# DIY_BLE_Keyboard.net
KiCad netlist of a schematic drawn in Altium Designer
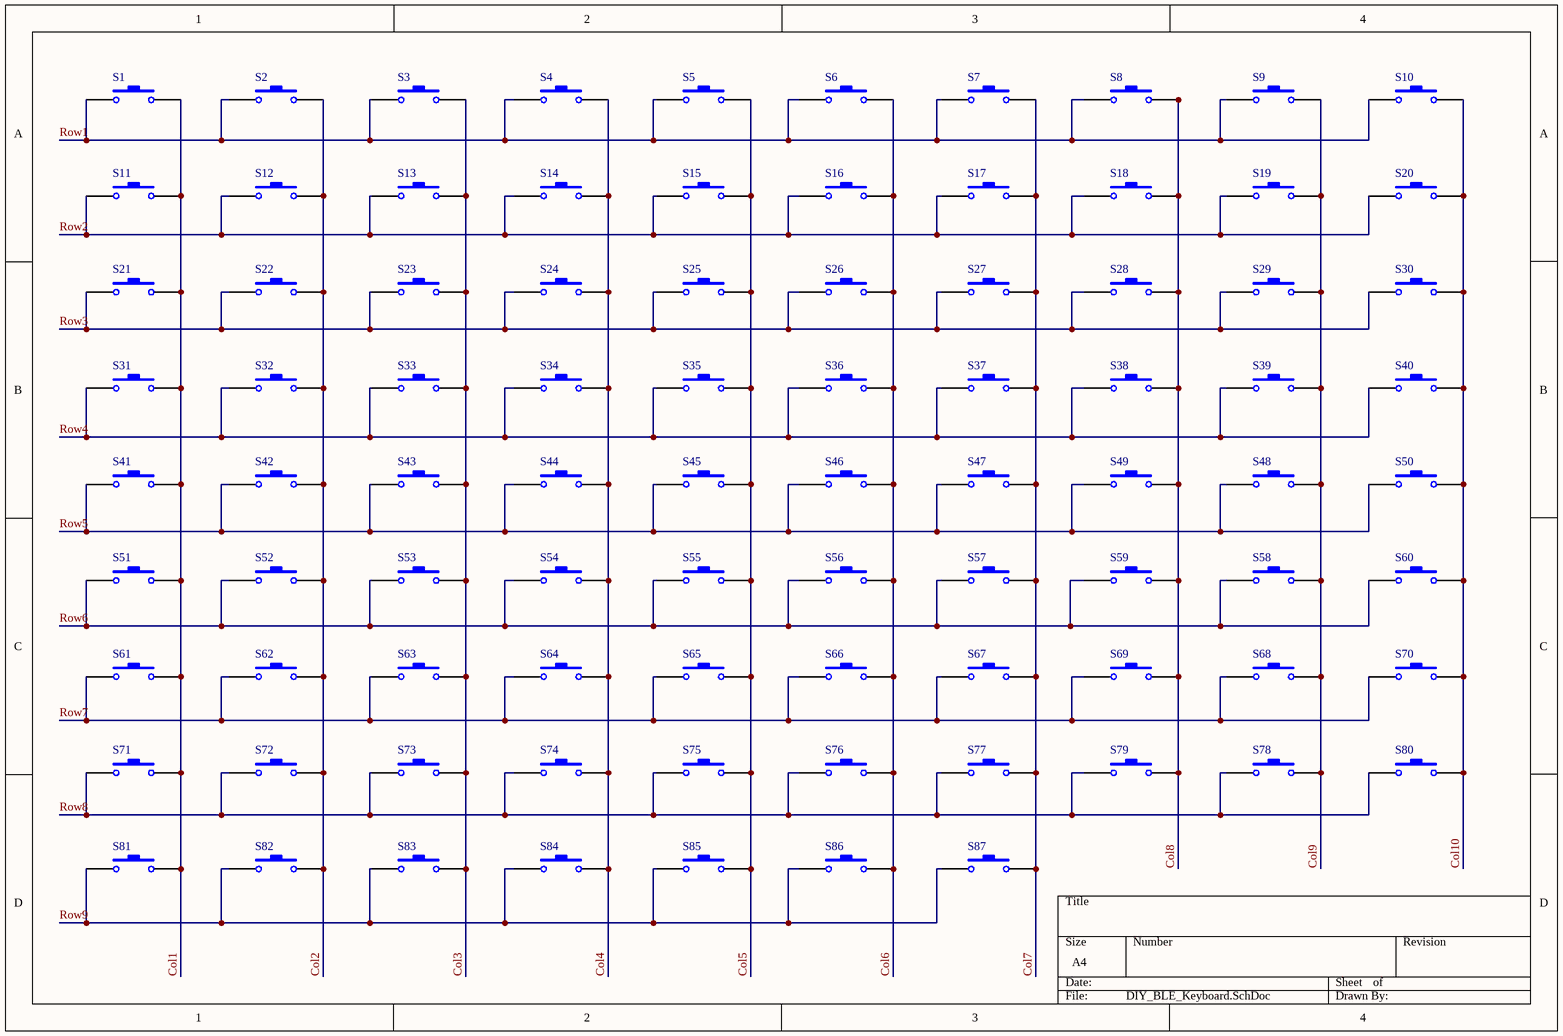
[diagram p0: DIY_BLE_Keyboard.SchDoc]

(export (version "E")
  (design (tool "Eeschema 10.0.6"))
  (components
    (comp (ref "S1")
      (value "SW-PB")
      (footprint "MX_SW-4")
      (description "Switch")
      (fields (field (name "PUBLISHER") "Altium Limited"))
      (libsource (lib "Miscellaneous Devices") (part "SW-PB"))
    )
    (comp (ref "S2")
      (value "SW-PB")
      (footprint "MX_SW-4")
      (description "Switch")
      (fields (field (name "PUBLISHER") "Altium Limited"))
      (libsource (lib "Miscellaneous Devices") (part "SW-PB"))
    )
    (comp (ref "S3")
      (value "SW-PB")
      (footprint "MX_SW-4")
      (description "Switch")
      (fields (field (name "PUBLISHER") "Altium Limited"))
      (libsource (lib "Miscellaneous Devices") (part "SW-PB"))
    )
    (comp (ref "S4")
      (value "SW-PB")
      (footprint "MX_SW-4")
      (description "Switch")
      (fields (field (name "PUBLISHER") "Altium Limited"))
      (libsource (lib "Miscellaneous Devices") (part "SW-PB"))
    )
    (comp (ref "S5")
      (value "SW-PB")
      (footprint "MX_SW-4")
      (description "Switch")
      (fields (field (name "PUBLISHER") "Altium Limited"))
      (libsource (lib "Miscellaneous Devices") (part "SW-PB"))
    )
    (comp (ref "S6")
      (value "SW-PB")
      (footprint "MX_SW-4")
      (description "Switch")
      (fields (field (name "PUBLISHER") "Altium Limited"))
      (libsource (lib "Miscellaneous Devices") (part "SW-PB"))
    )
    (comp (ref "S7")
      (value "SW-PB")
      (footprint "MX_SW-4")
      (description "Switch")
      (fields (field (name "PUBLISHER") "Altium Limited"))
      (libsource (lib "Miscellaneous Devices") (part "SW-PB"))
    )
    (comp (ref "S8")
      (value "SW-PB")
      (footprint "MX_SW-4")
      (description "Switch")
      (fields (field (name "PUBLISHER") "Altium Limited"))
      (libsource (lib "Miscellaneous Devices") (part "SW-PB"))
    )
    (comp (ref "S9")
      (value "SW-PB")
      (footprint "MX_SW-4")
      (description "Switch")
      (fields (field (name "PUBLISHER") "Altium Limited"))
      (libsource (lib "Miscellaneous Devices") (part "SW-PB"))
    )
    (comp (ref "S10")
      (value "SW-PB")
      (footprint "MX_SW-4")
      (description "Switch")
      (fields (field (name "PUBLISHER") "Altium Limited"))
      (libsource (lib "Miscellaneous Devices") (part "SW-PB"))
    )
    (comp (ref "S11")
      (value "SW-PB")
      (footprint "MX_SW-4")
      (description "Switch")
      (fields (field (name "PUBLISHER") "Altium Limited"))
      (libsource (lib "Miscellaneous Devices") (part "SW-PB"))
    )
    (comp (ref "S12")
      (value "SW-PB")
      (footprint "MX_SW-4")
      (description "Switch")
      (fields (field (name "PUBLISHER") "Altium Limited"))
      (libsource (lib "Miscellaneous Devices") (part "SW-PB"))
    )
    (comp (ref "S13")
      (value "SW-PB")
      (footprint "MX_SW-4")
      (description "Switch")
      (fields (field (name "PUBLISHER") "Altium Limited"))
      (libsource (lib "Miscellaneous Devices") (part "SW-PB"))
    )
    (comp (ref "S14")
      (value "SW-PB")
      (footprint "MX_SW-4")
      (description "Switch")
      (fields (field (name "PUBLISHER") "Altium Limited"))
      (libsource (lib "Miscellaneous Devices") (part "SW-PB"))
    )
    (comp (ref "S15")
      (value "SW-PB")
      (footprint "MX_SW-4")
      (description "Switch")
      (fields (field (name "PUBLISHER") "Altium Limited"))
      (libsource (lib "Miscellaneous Devices") (part "SW-PB"))
    )
    (comp (ref "S16")
      (value "SW-PB")
      (footprint "MX_SW-4")
      (description "Switch")
      (fields (field (name "PUBLISHER") "Altium Limited"))
      (libsource (lib "Miscellaneous Devices") (part "SW-PB"))
    )
    (comp (ref "S17")
      (value "SW-PB")
      (footprint "MX_SW-4")
      (description "Switch")
      (fields (field (name "PUBLISHER") "Altium Limited"))
      (libsource (lib "Miscellaneous Devices") (part "SW-PB"))
    )
    (comp (ref "S18")
      (value "SW-PB")
      (footprint "MX_SW-4")
      (description "Switch")
      (fields (field (name "PUBLISHER") "Altium Limited"))
      (libsource (lib "Miscellaneous Devices") (part "SW-PB"))
    )
    (comp (ref "S19")
      (value "SW-PB")
      (footprint "MX_SW-4")
      (description "Switch")
      (fields (field (name "PUBLISHER") "Altium Limited"))
      (libsource (lib "Miscellaneous Devices") (part "SW-PB"))
    )
    (comp (ref "S20")
      (value "SW-PB")
      (footprint "MX_SW-4")
      (description "Switch")
      (fields (field (name "PUBLISHER") "Altium Limited"))
      (libsource (lib "Miscellaneous Devices") (part "SW-PB"))
    )
    (comp (ref "S21")
      (value "SW-PB")
      (footprint "MX_SW-4")
      (description "Switch")
      (fields (field (name "PUBLISHER") "Altium Limited"))
      (libsource (lib "Miscellaneous Devices") (part "SW-PB"))
    )
    (comp (ref "S22")
      (value "SW-PB")
      (footprint "MX_SW-4")
      (description "Switch")
      (fields (field (name "PUBLISHER") "Altium Limited"))
      (libsource (lib "Miscellaneous Devices") (part "SW-PB"))
    )
    (comp (ref "S23")
      (value "SW-PB")
      (footprint "MX_SW-4")
      (description "Switch")
      (fields (field (name "PUBLISHER") "Altium Limited"))
      (libsource (lib "Miscellaneous Devices") (part "SW-PB"))
    )
    (comp (ref "S24")
      (value "SW-PB")
      (footprint "MX_SW-4")
      (description "Switch")
      (fields (field (name "PUBLISHER") "Altium Limited"))
      (libsource (lib "Miscellaneous Devices") (part "SW-PB"))
    )
    (comp (ref "S25")
      (value "SW-PB")
      (footprint "MX_SW-4")
      (description "Switch")
      (fields (field (name "PUBLISHER") "Altium Limited"))
      (libsource (lib "Miscellaneous Devices") (part "SW-PB"))
    )
    (comp (ref "S26")
      (value "SW-PB")
      (footprint "MX_SW-4")
      (description "Switch")
      (fields (field (name "PUBLISHER") "Altium Limited"))
      (libsource (lib "Miscellaneous Devices") (part "SW-PB"))
    )
    (comp (ref "S27")
      (value "SW-PB")
      (footprint "MX_SW-4")
      (description "Switch")
      (fields (field (name "PUBLISHER") "Altium Limited"))
      (libsource (lib "Miscellaneous Devices") (part "SW-PB"))
    )
    (comp (ref "S28")
      (value "SW-PB")
      (footprint "MX_SW-4")
      (description "Switch")
      (fields (field (name "PUBLISHER") "Altium Limited"))
      (libsource (lib "Miscellaneous Devices") (part "SW-PB"))
    )
    (comp (ref "S29")
      (value "SW-PB")
      (footprint "MX_SW-4")
      (description "Switch")
      (fields (field (name "PUBLISHER") "Altium Limited"))
      (libsource (lib "Miscellaneous Devices") (part "SW-PB"))
    )
    (comp (ref "S30")
      (value "SW-PB")
      (footprint "MX_SW-4")
      (description "Switch")
      (fields (field (name "PUBLISHER") "Altium Limited"))
      (libsource (lib "Miscellaneous Devices") (part "SW-PB"))
    )
    (comp (ref "S31")
      (value "SW-PB")
      (footprint "MX_SW-4")
      (description "Switch")
      (fields (field (name "PUBLISHER") "Altium Limited"))
      (libsource (lib "Miscellaneous Devices") (part "SW-PB"))
    )
    (comp (ref "S32")
      (value "SW-PB")
      (footprint "MX_SW-4")
      (description "Switch")
      (fields (field (name "PUBLISHER") "Altium Limited"))
      (libsource (lib "Miscellaneous Devices") (part "SW-PB"))
    )
    (comp (ref "S33")
      (value "SW-PB")
      (footprint "MX_SW-4")
      (description "Switch")
      (fields (field (name "PUBLISHER") "Altium Limited"))
      (libsource (lib "Miscellaneous Devices") (part "SW-PB"))
    )
    (comp (ref "S34")
      (value "SW-PB")
      (footprint "MX_SW-4")
      (description "Switch")
      (fields (field (name "PUBLISHER") "Altium Limited"))
      (libsource (lib "Miscellaneous Devices") (part "SW-PB"))
    )
    (comp (ref "S35")
      (value "SW-PB")
      (footprint "MX_SW-4")
      (description "Switch")
      (fields (field (name "PUBLISHER") "Altium Limited"))
      (libsource (lib "Miscellaneous Devices") (part "SW-PB"))
    )
    (comp (ref "S36")
      (value "SW-PB")
      (footprint "MX_SW-4")
      (description "Switch")
      (fields (field (name "PUBLISHER") "Altium Limited"))
      (libsource (lib "Miscellaneous Devices") (part "SW-PB"))
    )
    (comp (ref "S37")
      (value "SW-PB")
      (footprint "MX_SW-4")
      (description "Switch")
      (fields (field (name "PUBLISHER") "Altium Limited"))
      (libsource (lib "Miscellaneous Devices") (part "SW-PB"))
    )
    (comp (ref "S38")
      (value "SW-PB")
      (footprint "MX_SW-4")
      (description "Switch")
      (fields (field (name "PUBLISHER") "Altium Limited"))
      (libsource (lib "Miscellaneous Devices") (part "SW-PB"))
    )
    (comp (ref "S39")
      (value "SW-PB")
      (footprint "MX_SW-4")
      (description "Switch")
      (fields (field (name "PUBLISHER") "Altium Limited"))
      (libsource (lib "Miscellaneous Devices") (part "SW-PB"))
    )
    (comp (ref "S40")
      (value "SW-PB")
      (footprint "MX_SW-4")
      (description "Switch")
      (fields (field (name "PUBLISHER") "Altium Limited"))
      (libsource (lib "Miscellaneous Devices") (part "SW-PB"))
    )
    (comp (ref "S41")
      (value "SW-PB")
      (footprint "MX_SW-4")
      (description "Switch")
      (fields (field (name "PUBLISHER") "Altium Limited"))
      (libsource (lib "Miscellaneous Devices") (part "SW-PB"))
    )
    (comp (ref "S42")
      (value "SW-PB")
      (footprint "MX_SW-4")
      (description "Switch")
      (fields (field (name "PUBLISHER") "Altium Limited"))
      (libsource (lib "Miscellaneous Devices") (part "SW-PB"))
    )
    (comp (ref "S43")
      (value "SW-PB")
      (footprint "MX_SW-4")
      (description "Switch")
      (fields (field (name "PUBLISHER") "Altium Limited"))
      (libsource (lib "Miscellaneous Devices") (part "SW-PB"))
    )
    (comp (ref "S44")
      (value "SW-PB")
      (footprint "MX_SW-4")
      (description "Switch")
      (fields (field (name "PUBLISHER") "Altium Limited"))
      (libsource (lib "Miscellaneous Devices") (part "SW-PB"))
    )
    (comp (ref "S45")
      (value "SW-PB")
      (footprint "MX_SW-4")
      (description "Switch")
      (fields (field (name "PUBLISHER") "Altium Limited"))
      (libsource (lib "Miscellaneous Devices") (part "SW-PB"))
    )
    (comp (ref "S46")
      (value "SW-PB")
      (footprint "MX_SW-4")
      (description "Switch")
      (fields (field (name "PUBLISHER") "Altium Limited"))
      (libsource (lib "Miscellaneous Devices") (part "SW-PB"))
    )
    (comp (ref "S47")
      (value "SW-PB")
      (footprint "MX_SW-4")
      (description "Switch")
      (fields (field (name "PUBLISHER") "Altium Limited"))
      (libsource (lib "Miscellaneous Devices") (part "SW-PB"))
    )
    (comp (ref "S48")
      (value "SW-PB")
      (footprint "MX_SW-4")
      (description "Switch")
      (fields (field (name "PUBLISHER") "Altium Limited"))
      (libsource (lib "Miscellaneous Devices") (part "SW-PB"))
    )
    (comp (ref "S49")
      (value "SW-PB")
      (footprint "MX_SW-4")
      (description "Switch")
      (fields (field (name "PUBLISHER") "Altium Limited"))
      (libsource (lib "Miscellaneous Devices") (part "SW-PB"))
    )
    (comp (ref "S50")
      (value "SW-PB")
      (footprint "MX_SW-4")
      (description "Switch")
      (fields (field (name "PUBLISHER") "Altium Limited"))
      (libsource (lib "Miscellaneous Devices") (part "SW-PB"))
    )
    (comp (ref "S51")
      (value "SW-PB")
      (footprint "MX_SW-4")
      (description "Switch")
      (fields (field (name "PUBLISHER") "Altium Limited"))
      (libsource (lib "Miscellaneous Devices") (part "SW-PB"))
    )
    (comp (ref "S52")
      (value "SW-PB")
      (footprint "MX_SW-4")
      (description "Switch")
      (fields (field (name "PUBLISHER") "Altium Limited"))
      (libsource (lib "Miscellaneous Devices") (part "SW-PB"))
    )
    (comp (ref "S53")
      (value "SW-PB")
      (footprint "MX_SW-4")
      (description "Switch")
      (fields (field (name "PUBLISHER") "Altium Limited"))
      (libsource (lib "Miscellaneous Devices") (part "SW-PB"))
    )
    (comp (ref "S54")
      (value "SW-PB")
      (footprint "MX_SW-4")
      (description "Switch")
      (fields (field (name "PUBLISHER") "Altium Limited"))
      (libsource (lib "Miscellaneous Devices") (part "SW-PB"))
    )
    (comp (ref "S55")
      (value "SW-PB")
      (footprint "MX_SW-4")
      (description "Switch")
      (fields (field (name "PUBLISHER") "Altium Limited"))
      (libsource (lib "Miscellaneous Devices") (part "SW-PB"))
    )
    (comp (ref "S56")
      (value "SW-PB")
      (footprint "MX_SW-4")
      (description "Switch")
      (fields (field (name "PUBLISHER") "Altium Limited"))
      (libsource (lib "Miscellaneous Devices") (part "SW-PB"))
    )
    (comp (ref "S57")
      (value "SW-PB")
      (footprint "MX_SW-4")
      (description "Switch")
      (fields (field (name "PUBLISHER") "Altium Limited"))
      (libsource (lib "Miscellaneous Devices") (part "SW-PB"))
    )
    (comp (ref "S58")
      (value "SW-PB")
      (footprint "MX_SW-4")
      (description "Switch")
      (fields (field (name "PUBLISHER") "Altium Limited"))
      (libsource (lib "Miscellaneous Devices") (part "SW-PB"))
    )
    (comp (ref "S59")
      (value "SW-PB")
      (footprint "MX_SW-4")
      (description "Switch")
      (fields (field (name "PUBLISHER") "Altium Limited"))
      (libsource (lib "Miscellaneous Devices") (part "SW-PB"))
    )
    (comp (ref "S60")
      (value "SW-PB")
      (footprint "MX_SW-4")
      (description "Switch")
      (fields (field (name "PUBLISHER") "Altium Limited"))
      (libsource (lib "Miscellaneous Devices") (part "SW-PB"))
    )
    (comp (ref "S61")
      (value "SW-PB")
      (footprint "MX_SW-4")
      (description "Switch")
      (fields (field (name "PUBLISHER") "Altium Limited"))
      (libsource (lib "Miscellaneous Devices") (part "SW-PB"))
    )
    (comp (ref "S62")
      (value "SW-PB")
      (footprint "MX_SW-4")
      (description "Switch")
      (fields (field (name "PUBLISHER") "Altium Limited"))
      (libsource (lib "Miscellaneous Devices") (part "SW-PB"))
    )
    (comp (ref "S63")
      (value "SW-PB")
      (footprint "MX_SW-4")
      (description "Switch")
      (fields (field (name "PUBLISHER") "Altium Limited"))
      (libsource (lib "Miscellaneous Devices") (part "SW-PB"))
    )
    (comp (ref "S64")
      (value "SW-PB")
      (footprint "MX_SW-4")
      (description "Switch")
      (fields (field (name "PUBLISHER") "Altium Limited"))
      (libsource (lib "Miscellaneous Devices") (part "SW-PB"))
    )
    (comp (ref "S65")
      (value "SW-PB")
      (footprint "MX_SW-4")
      (description "Switch")
      (fields (field (name "PUBLISHER") "Altium Limited"))
      (libsource (lib "Miscellaneous Devices") (part "SW-PB"))
    )
    (comp (ref "S66")
      (value "SW-PB")
      (footprint "MX_SW-4")
      (description "Switch")
      (fields (field (name "PUBLISHER") "Altium Limited"))
      (libsource (lib "Miscellaneous Devices") (part "SW-PB"))
    )
    (comp (ref "S67")
      (value "SW-PB")
      (footprint "MX_SW-4")
      (description "Switch")
      (fields (field (name "PUBLISHER") "Altium Limited"))
      (libsource (lib "Miscellaneous Devices") (part "SW-PB"))
    )
    (comp (ref "S68")
      (value "SW-PB")
      (footprint "MX_SW-4")
      (description "Switch")
      (fields (field (name "PUBLISHER") "Altium Limited"))
      (libsource (lib "Miscellaneous Devices") (part "SW-PB"))
    )
    (comp (ref "S69")
      (value "SW-PB")
      (footprint "MX_SW-4")
      (description "Switch")
      (fields (field (name "PUBLISHER") "Altium Limited"))
      (libsource (lib "Miscellaneous Devices") (part "SW-PB"))
    )
    (comp (ref "S70")
      (value "SW-PB")
      (footprint "MX_SW-4")
      (description "Switch")
      (fields (field (name "PUBLISHER") "Altium Limited"))
      (libsource (lib "Miscellaneous Devices") (part "SW-PB"))
    )
    (comp (ref "S71")
      (value "SW-PB")
      (footprint "MX_SW-4")
      (description "Switch")
      (fields (field (name "PUBLISHER") "Altium Limited"))
      (libsource (lib "Miscellaneous Devices") (part "SW-PB"))
    )
    (comp (ref "S72")
      (value "SW-PB")
      (footprint "MX_SW-4")
      (description "Switch")
      (fields (field (name "PUBLISHER") "Altium Limited"))
      (libsource (lib "Miscellaneous Devices") (part "SW-PB"))
    )
    (comp (ref "S73")
      (value "SW-PB")
      (footprint "MX_SW-4")
      (description "Switch")
      (fields (field (name "PUBLISHER") "Altium Limited"))
      (libsource (lib "Miscellaneous Devices") (part "SW-PB"))
    )
    (comp (ref "S74")
      (value "SW-PB")
      (footprint "MX_SW-4")
      (description "Switch")
      (fields (field (name "PUBLISHER") "Altium Limited"))
      (libsource (lib "Miscellaneous Devices") (part "SW-PB"))
    )
    (comp (ref "S75")
      (value "SW-PB")
      (footprint "MX_SW-4")
      (description "Switch")
      (fields (field (name "PUBLISHER") "Altium Limited"))
      (libsource (lib "Miscellaneous Devices") (part "SW-PB"))
    )
    (comp (ref "S76")
      (value "SW-PB")
      (footprint "MX_SW-4")
      (description "Switch")
      (fields (field (name "PUBLISHER") "Altium Limited"))
      (libsource (lib "Miscellaneous Devices") (part "SW-PB"))
    )
    (comp (ref "S77")
      (value "SW-PB")
      (footprint "MX_SW-4")
      (description "Switch")
      (fields (field (name "PUBLISHER") "Altium Limited"))
      (libsource (lib "Miscellaneous Devices") (part "SW-PB"))
    )
    (comp (ref "S78")
      (value "SW-PB")
      (footprint "MX_SW-4")
      (description "Switch")
      (fields (field (name "PUBLISHER") "Altium Limited"))
      (libsource (lib "Miscellaneous Devices") (part "SW-PB"))
    )
    (comp (ref "S79")
      (value "SW-PB")
      (footprint "MX_SW-4")
      (description "Switch")
      (fields (field (name "PUBLISHER") "Altium Limited"))
      (libsource (lib "Miscellaneous Devices") (part "SW-PB"))
    )
    (comp (ref "S80")
      (value "SW-PB")
      (footprint "MX_SW-4")
      (description "Switch")
      (fields (field (name "PUBLISHER") "Altium Limited"))
      (libsource (lib "Miscellaneous Devices") (part "SW-PB"))
    )
    (comp (ref "S81")
      (value "SW-PB")
      (footprint "MX_SW-4")
      (description "Switch")
      (fields (field (name "PUBLISHER") "Altium Limited"))
      (libsource (lib "Miscellaneous Devices") (part "SW-PB"))
    )
    (comp (ref "S82")
      (value "SW-PB")
      (footprint "MX_SW-4")
      (description "Switch")
      (fields (field (name "PUBLISHER") "Altium Limited"))
      (libsource (lib "Miscellaneous Devices") (part "SW-PB"))
    )
    (comp (ref "S83")
      (value "SW-PB")
      (footprint "MX_SW-4")
      (description "Switch")
      (fields (field (name "PUBLISHER") "Altium Limited"))
      (libsource (lib "Miscellaneous Devices") (part "SW-PB"))
    )
    (comp (ref "S84")
      (value "SW-PB")
      (footprint "MX_SW-4")
      (description "Switch")
      (fields (field (name "PUBLISHER") "Altium Limited"))
      (libsource (lib "Miscellaneous Devices") (part "SW-PB"))
    )
    (comp (ref "S85")
      (value "SW-PB")
      (footprint "MX_SW-4")
      (description "Switch")
      (fields (field (name "PUBLISHER") "Altium Limited"))
      (libsource (lib "Miscellaneous Devices") (part "SW-PB"))
    )
    (comp (ref "S86")
      (value "SW-PB")
      (footprint "MX_SW-4")
      (description "Switch")
      (fields (field (name "PUBLISHER") "Altium Limited"))
      (libsource (lib "Miscellaneous Devices") (part "SW-PB"))
    )
    (comp (ref "S87")
      (value "SW-PB")
      (footprint "MX_SW-4")
      (description "Switch")
      (fields (field (name "PUBLISHER") "Altium Limited"))
      (libsource (lib "Miscellaneous Devices") (part "SW-PB"))
    )
  )
  (nets
    (net (code "1") (name "/Col1") (class "Default")
      (node (ref "S1") (pin "2") (pinfunction "2_2") (pintype "passive"))
      (node (ref "S11") (pin "2") (pinfunction "2_2") (pintype "passive"))
      (node (ref "S21") (pin "2") (pinfunction "2_2") (pintype "passive"))
      (node (ref "S31") (pin "2") (pinfunction "2_2") (pintype "passive"))
      (node (ref "S41") (pin "2") (pinfunction "2_2") (pintype "passive"))
      (node (ref "S51") (pin "2") (pinfunction "2_2") (pintype "passive"))
      (node (ref "S61") (pin "2") (pinfunction "2_2") (pintype "passive"))
      (node (ref "S71") (pin "2") (pinfunction "2_2") (pintype "passive"))
      (node (ref "S81") (pin "2") (pinfunction "2_2") (pintype "passive"))
    )
    (net (code "2") (name "/Col2") (class "Default")
      (node (ref "S12") (pin "2") (pinfunction "2_2") (pintype "passive"))
      (node (ref "S2") (pin "2") (pinfunction "2_2") (pintype "passive"))
      (node (ref "S22") (pin "2") (pinfunction "2_2") (pintype "passive"))
      (node (ref "S32") (pin "2") (pinfunction "2_2") (pintype "passive"))
      (node (ref "S42") (pin "2") (pinfunction "2_2") (pintype "passive"))
      (node (ref "S52") (pin "2") (pinfunction "2_2") (pintype "passive"))
      (node (ref "S62") (pin "2") (pinfunction "2_2") (pintype "passive"))
      (node (ref "S72") (pin "2") (pinfunction "2_2") (pintype "passive"))
      (node (ref "S82") (pin "2") (pinfunction "2_2") (pintype "passive"))
    )
    (net (code "3") (name "/Col3") (class "Default")
      (node (ref "S13") (pin "2") (pinfunction "2_2") (pintype "passive"))
      (node (ref "S23") (pin "2") (pinfunction "2_2") (pintype "passive"))
      (node (ref "S3") (pin "2") (pinfunction "2_2") (pintype "passive"))
      (node (ref "S33") (pin "2") (pinfunction "2_2") (pintype "passive"))
      (node (ref "S43") (pin "2") (pinfunction "2_2") (pintype "passive"))
      (node (ref "S53") (pin "2") (pinfunction "2_2") (pintype "passive"))
      (node (ref "S63") (pin "2") (pinfunction "2_2") (pintype "passive"))
      (node (ref "S73") (pin "2") (pinfunction "2_2") (pintype "passive"))
      (node (ref "S83") (pin "2") (pinfunction "2_2") (pintype "passive"))
    )
    (net (code "4") (name "/Col4") (class "Default")
      (node (ref "S14") (pin "2") (pinfunction "2_2") (pintype "passive"))
      (node (ref "S24") (pin "2") (pinfunction "2_2") (pintype "passive"))
      (node (ref "S34") (pin "2") (pinfunction "2_2") (pintype "passive"))
      (node (ref "S4") (pin "2") (pinfunction "2_2") (pintype "passive"))
      (node (ref "S44") (pin "2") (pinfunction "2_2") (pintype "passive"))
      (node (ref "S54") (pin "2") (pinfunction "2_2") (pintype "passive"))
      (node (ref "S64") (pin "2") (pinfunction "2_2") (pintype "passive"))
      (node (ref "S74") (pin "2") (pinfunction "2_2") (pintype "passive"))
      (node (ref "S84") (pin "2") (pinfunction "2_2") (pintype "passive"))
    )
    (net (code "5") (name "/Col5") (class "Default")
      (node (ref "S15") (pin "2") (pinfunction "2_2") (pintype "passive"))
      (node (ref "S25") (pin "2") (pinfunction "2_2") (pintype "passive"))
      (node (ref "S35") (pin "2") (pinfunction "2_2") (pintype "passive"))
      (node (ref "S45") (pin "2") (pinfunction "2_2") (pintype "passive"))
      (node (ref "S5") (pin "2") (pinfunction "2_2") (pintype "passive"))
      (node (ref "S55") (pin "2") (pinfunction "2_2") (pintype "passive"))
      (node (ref "S65") (pin "2") (pinfunction "2_2") (pintype "passive"))
      (node (ref "S75") (pin "2") (pinfunction "2_2") (pintype "passive"))
      (node (ref "S85") (pin "2") (pinfunction "2_2") (pintype "passive"))
    )
    (net (code "6") (name "/Col6") (class "Default")
      (node (ref "S16") (pin "2") (pinfunction "2_2") (pintype "passive"))
      (node (ref "S26") (pin "2") (pinfunction "2_2") (pintype "passive"))
      (node (ref "S36") (pin "2") (pinfunction "2_2") (pintype "passive"))
      (node (ref "S46") (pin "2") (pinfunction "2_2") (pintype "passive"))
      (node (ref "S56") (pin "2") (pinfunction "2_2") (pintype "passive"))
      (node (ref "S6") (pin "2") (pinfunction "2_2") (pintype "passive"))
      (node (ref "S66") (pin "2") (pinfunction "2_2") (pintype "passive"))
      (node (ref "S76") (pin "2") (pinfunction "2_2") (pintype "passive"))
      (node (ref "S86") (pin "2") (pinfunction "2_2") (pintype "passive"))
    )
    (net (code "7") (name "/Col7") (class "Default")
      (node (ref "S17") (pin "2") (pinfunction "2_2") (pintype "passive"))
      (node (ref "S27") (pin "2") (pinfunction "2_2") (pintype "passive"))
      (node (ref "S37") (pin "2") (pinfunction "2_2") (pintype "passive"))
      (node (ref "S47") (pin "2") (pinfunction "2_2") (pintype "passive"))
      (node (ref "S57") (pin "2") (pinfunction "2_2") (pintype "passive"))
      (node (ref "S67") (pin "2") (pinfunction "2_2") (pintype "passive"))
      (node (ref "S7") (pin "2") (pinfunction "2_2") (pintype "passive"))
      (node (ref "S77") (pin "2") (pinfunction "2_2") (pintype "passive"))
      (node (ref "S87") (pin "2") (pinfunction "2_2") (pintype "passive"))
    )
    (net (code "8") (name "/Col8") (class "Default")
      (node (ref "S18") (pin "2") (pinfunction "2_2") (pintype "passive"))
      (node (ref "S28") (pin "2") (pinfunction "2_2") (pintype "passive"))
      (node (ref "S38") (pin "2") (pinfunction "2_2") (pintype "passive"))
      (node (ref "S49") (pin "2") (pinfunction "2_2") (pintype "passive"))
      (node (ref "S59") (pin "2") (pinfunction "2_2") (pintype "passive"))
      (node (ref "S69") (pin "2") (pinfunction "2_2") (pintype "passive"))
      (node (ref "S79") (pin "2") (pinfunction "2_2") (pintype "passive"))
      (node (ref "S8") (pin "2") (pinfunction "2_2") (pintype "passive"))
    )
    (net (code "9") (name "/Col9") (class "Default")
      (node (ref "S19") (pin "2") (pinfunction "2_2") (pintype "passive"))
      (node (ref "S29") (pin "2") (pinfunction "2_2") (pintype "passive"))
      (node (ref "S39") (pin "2") (pinfunction "2_2") (pintype "passive"))
      (node (ref "S48") (pin "2") (pinfunction "2_2") (pintype "passive"))
      (node (ref "S58") (pin "2") (pinfunction "2_2") (pintype "passive"))
      (node (ref "S68") (pin "2") (pinfunction "2_2") (pintype "passive"))
      (node (ref "S78") (pin "2") (pinfunction "2_2") (pintype "passive"))
      (node (ref "S9") (pin "2") (pinfunction "2_2") (pintype "passive"))
    )
    (net (code "10") (name "/Col10") (class "Default")
      (node (ref "S10") (pin "2") (pinfunction "2_2") (pintype "passive"))
      (node (ref "S20") (pin "2") (pinfunction "2_2") (pintype "passive"))
      (node (ref "S30") (pin "2") (pinfunction "2_2") (pintype "passive"))
      (node (ref "S40") (pin "2") (pinfunction "2_2") (pintype "passive"))
      (node (ref "S50") (pin "2") (pinfunction "2_2") (pintype "passive"))
      (node (ref "S60") (pin "2") (pinfunction "2_2") (pintype "passive"))
      (node (ref "S70") (pin "2") (pinfunction "2_2") (pintype "passive"))
      (node (ref "S80") (pin "2") (pinfunction "2_2") (pintype "passive"))
    )
    (net (code "11") (name "/Row1") (class "Default")
      (node (ref "S1") (pin "1") (pinfunction "1_1") (pintype "passive"))
      (node (ref "S10") (pin "1") (pinfunction "1_1") (pintype "passive"))
      (node (ref "S2") (pin "1") (pinfunction "1_1") (pintype "passive"))
      (node (ref "S3") (pin "1") (pinfunction "1_1") (pintype "passive"))
      (node (ref "S4") (pin "1") (pinfunction "1_1") (pintype "passive"))
      (node (ref "S5") (pin "1") (pinfunction "1_1") (pintype "passive"))
      (node (ref "S6") (pin "1") (pinfunction "1_1") (pintype "passive"))
      (node (ref "S7") (pin "1") (pinfunction "1_1") (pintype "passive"))
      (node (ref "S8") (pin "1") (pinfunction "1_1") (pintype "passive"))
      (node (ref "S9") (pin "1") (pinfunction "1_1") (pintype "passive"))
    )
    (net (code "12") (name "/Row2") (class "Default")
      (node (ref "S11") (pin "1") (pinfunction "1_1") (pintype "passive"))
      (node (ref "S12") (pin "1") (pinfunction "1_1") (pintype "passive"))
      (node (ref "S13") (pin "1") (pinfunction "1_1") (pintype "passive"))
      (node (ref "S14") (pin "1") (pinfunction "1_1") (pintype "passive"))
      (node (ref "S15") (pin "1") (pinfunction "1_1") (pintype "passive"))
      (node (ref "S16") (pin "1") (pinfunction "1_1") (pintype "passive"))
      (node (ref "S17") (pin "1") (pinfunction "1_1") (pintype "passive"))
      (node (ref "S18") (pin "1") (pinfunction "1_1") (pintype "passive"))
      (node (ref "S19") (pin "1") (pinfunction "1_1") (pintype "passive"))
      (node (ref "S20") (pin "1") (pinfunction "1_1") (pintype "passive"))
    )
    (net (code "13") (name "/Row3") (class "Default")
      (node (ref "S21") (pin "1") (pinfunction "1_1") (pintype "passive"))
      (node (ref "S22") (pin "1") (pinfunction "1_1") (pintype "passive"))
      (node (ref "S23") (pin "1") (pinfunction "1_1") (pintype "passive"))
      (node (ref "S24") (pin "1") (pinfunction "1_1") (pintype "passive"))
      (node (ref "S25") (pin "1") (pinfunction "1_1") (pintype "passive"))
      (node (ref "S26") (pin "1") (pinfunction "1_1") (pintype "passive"))
      (node (ref "S27") (pin "1") (pinfunction "1_1") (pintype "passive"))
      (node (ref "S28") (pin "1") (pinfunction "1_1") (pintype "passive"))
      (node (ref "S29") (pin "1") (pinfunction "1_1") (pintype "passive"))
      (node (ref "S30") (pin "1") (pinfunction "1_1") (pintype "passive"))
    )
    (net (code "14") (name "/Row4") (class "Default")
      (node (ref "S31") (pin "1") (pinfunction "1_1") (pintype "passive"))
      (node (ref "S32") (pin "1") (pinfunction "1_1") (pintype "passive"))
      (node (ref "S33") (pin "1") (pinfunction "1_1") (pintype "passive"))
      (node (ref "S34") (pin "1") (pinfunction "1_1") (pintype "passive"))
      (node (ref "S35") (pin "1") (pinfunction "1_1") (pintype "passive"))
      (node (ref "S36") (pin "1") (pinfunction "1_1") (pintype "passive"))
      (node (ref "S37") (pin "1") (pinfunction "1_1") (pintype "passive"))
      (node (ref "S38") (pin "1") (pinfunction "1_1") (pintype "passive"))
      (node (ref "S39") (pin "1") (pinfunction "1_1") (pintype "passive"))
      (node (ref "S40") (pin "1") (pinfunction "1_1") (pintype "passive"))
    )
    (net (code "15") (name "/Row5") (class "Default")
      (node (ref "S41") (pin "1") (pinfunction "1_1") (pintype "passive"))
      (node (ref "S42") (pin "1") (pinfunction "1_1") (pintype "passive"))
      (node (ref "S43") (pin "1") (pinfunction "1_1") (pintype "passive"))
      (node (ref "S44") (pin "1") (pinfunction "1_1") (pintype "passive"))
      (node (ref "S45") (pin "1") (pinfunction "1_1") (pintype "passive"))
      (node (ref "S46") (pin "1") (pinfunction "1_1") (pintype "passive"))
      (node (ref "S47") (pin "1") (pinfunction "1_1") (pintype "passive"))
      (node (ref "S48") (pin "1") (pinfunction "1_1") (pintype "passive"))
      (node (ref "S49") (pin "1") (pinfunction "1_1") (pintype "passive"))
      (node (ref "S50") (pin "1") (pinfunction "1_1") (pintype "passive"))
    )
    (net (code "16") (name "/Row6") (class "Default")
      (node (ref "S51") (pin "1") (pinfunction "1_1") (pintype "passive"))
      (node (ref "S52") (pin "1") (pinfunction "1_1") (pintype "passive"))
      (node (ref "S53") (pin "1") (pinfunction "1_1") (pintype "passive"))
      (node (ref "S54") (pin "1") (pinfunction "1_1") (pintype "passive"))
      (node (ref "S55") (pin "1") (pinfunction "1_1") (pintype "passive"))
      (node (ref "S56") (pin "1") (pinfunction "1_1") (pintype "passive"))
      (node (ref "S57") (pin "1") (pinfunction "1_1") (pintype "passive"))
      (node (ref "S58") (pin "1") (pinfunction "1_1") (pintype "passive"))
      (node (ref "S59") (pin "1") (pinfunction "1_1") (pintype "passive"))
      (node (ref "S60") (pin "1") (pinfunction "1_1") (pintype "passive"))
    )
    (net (code "17") (name "/Row7") (class "Default")
      (node (ref "S61") (pin "1") (pinfunction "1_1") (pintype "passive"))
      (node (ref "S62") (pin "1") (pinfunction "1_1") (pintype "passive"))
      (node (ref "S63") (pin "1") (pinfunction "1_1") (pintype "passive"))
      (node (ref "S64") (pin "1") (pinfunction "1_1") (pintype "passive"))
      (node (ref "S65") (pin "1") (pinfunction "1_1") (pintype "passive"))
      (node (ref "S66") (pin "1") (pinfunction "1_1") (pintype "passive"))
      (node (ref "S67") (pin "1") (pinfunction "1_1") (pintype "passive"))
      (node (ref "S68") (pin "1") (pinfunction "1_1") (pintype "passive"))
      (node (ref "S69") (pin "1") (pinfunction "1_1") (pintype "passive"))
      (node (ref "S70") (pin "1") (pinfunction "1_1") (pintype "passive"))
    )
    (net (code "18") (name "/Row8") (class "Default")
      (node (ref "S71") (pin "1") (pinfunction "1_1") (pintype "passive"))
      (node (ref "S72") (pin "1") (pinfunction "1_1") (pintype "passive"))
      (node (ref "S73") (pin "1") (pinfunction "1_1") (pintype "passive"))
      (node (ref "S74") (pin "1") (pinfunction "1_1") (pintype "passive"))
      (node (ref "S75") (pin "1") (pinfunction "1_1") (pintype "passive"))
      (node (ref "S76") (pin "1") (pinfunction "1_1") (pintype "passive"))
      (node (ref "S77") (pin "1") (pinfunction "1_1") (pintype "passive"))
      (node (ref "S78") (pin "1") (pinfunction "1_1") (pintype "passive"))
      (node (ref "S79") (pin "1") (pinfunction "1_1") (pintype "passive"))
      (node (ref "S80") (pin "1") (pinfunction "1_1") (pintype "passive"))
    )
    (net (code "19") (name "/Row9") (class "Default")
      (node (ref "S81") (pin "1") (pinfunction "1_1") (pintype "passive"))
      (node (ref "S82") (pin "1") (pinfunction "1_1") (pintype "passive"))
      (node (ref "S83") (pin "1") (pinfunction "1_1") (pintype "passive"))
      (node (ref "S84") (pin "1") (pinfunction "1_1") (pintype "passive"))
      (node (ref "S85") (pin "1") (pinfunction "1_1") (pintype "passive"))
      (node (ref "S86") (pin "1") (pinfunction "1_1") (pintype "passive"))
      (node (ref "S87") (pin "1") (pinfunction "1_1") (pintype "passive"))
    )
  )
)
